# extruder-controller.net
KiCad netlist of a schematic drawn in EAGLE
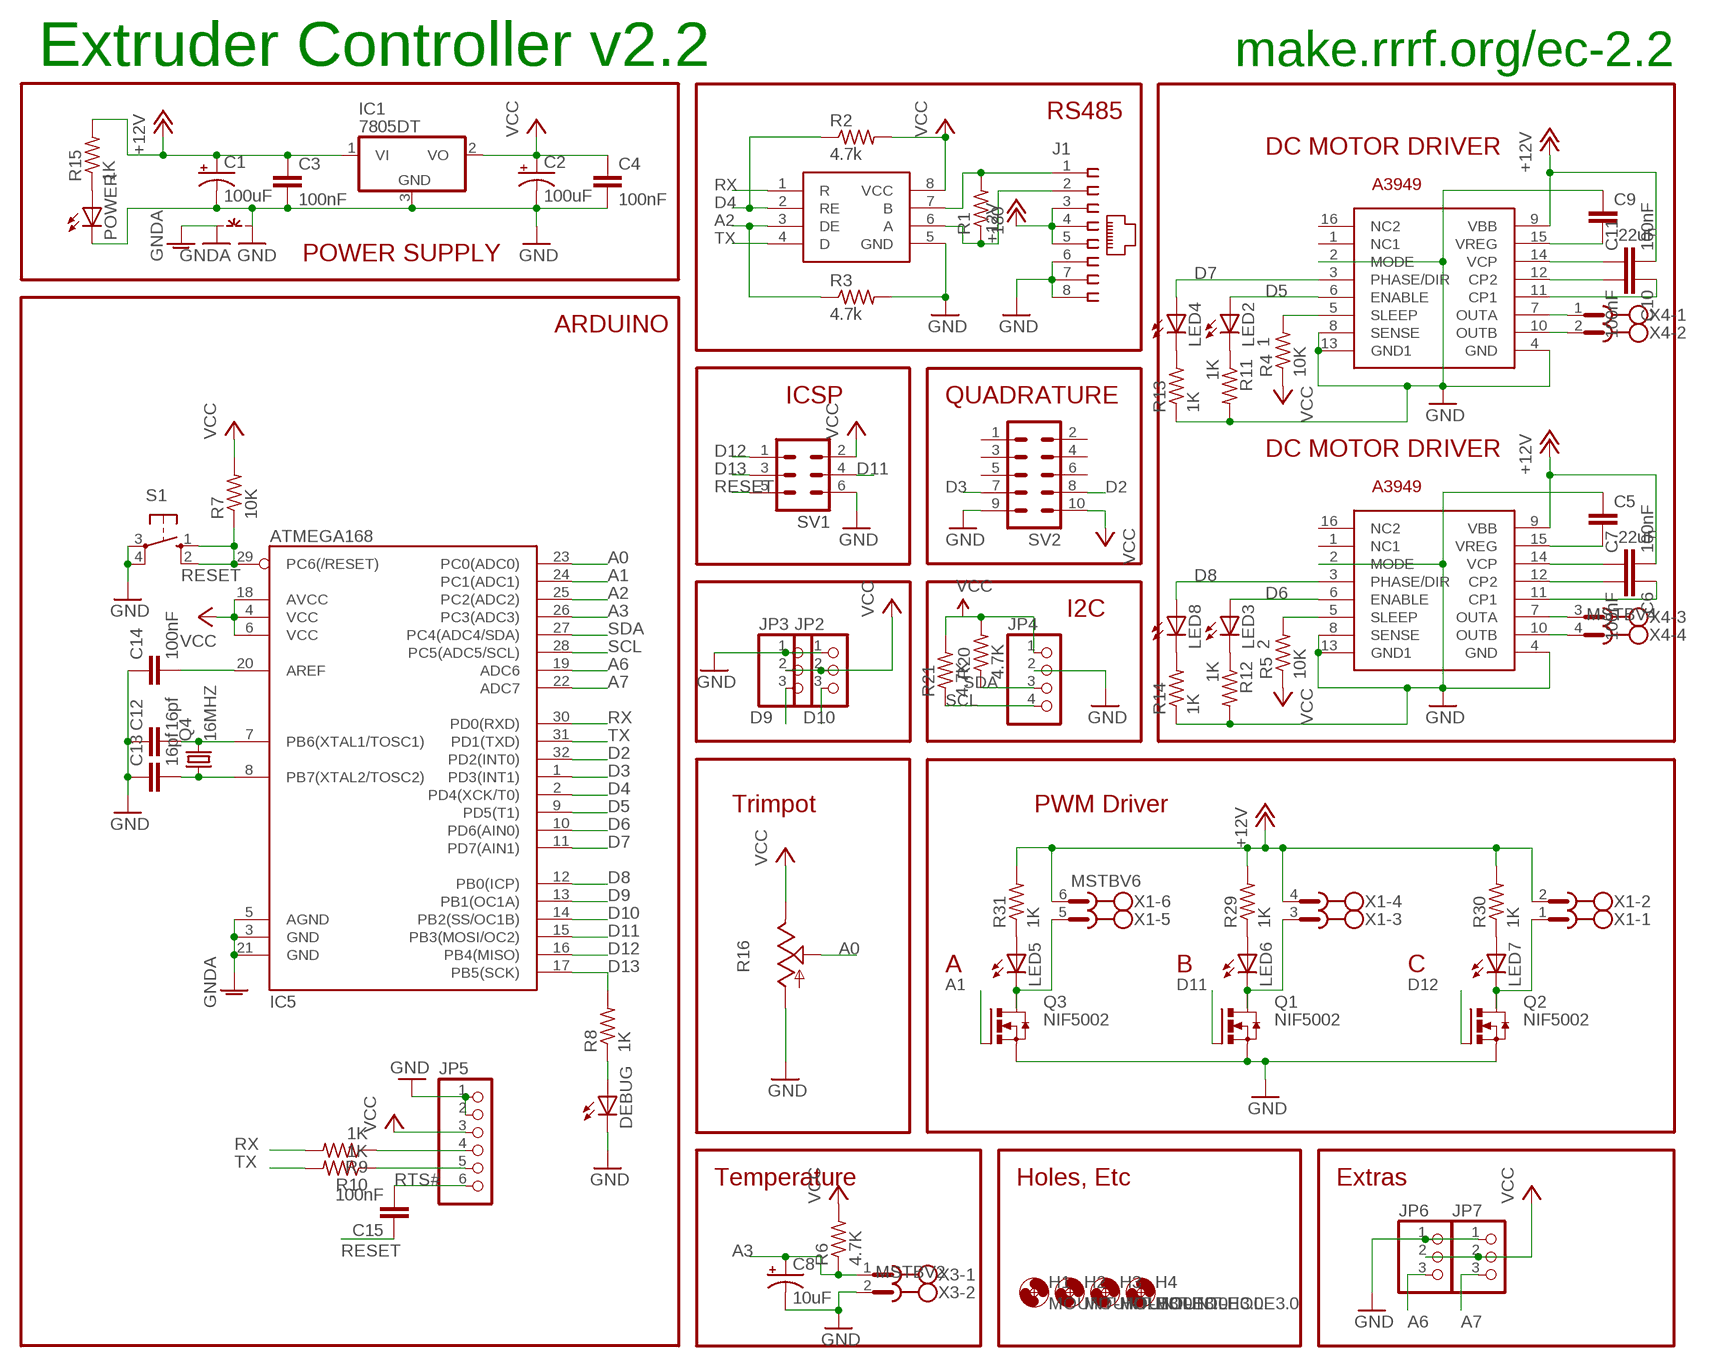
[diagram p0: schematic, sheet 1]

(export (version "E")
  (design (tool "Eeschema 10.0.6"))
  (components
    (comp (ref "C1")
      (value "100uF")
      (footprint "eagle-import:UD-10X10_NICHICON")
      (libsource (lib "eagle-import") (part "CPOL-USUD-10X10"))
    )
    (comp (ref "C2")
      (value "100uF")
      (footprint "eagle-import:UD-10X10_NICHICON")
      (libsource (lib "eagle-import") (part "CPOL-USUD-10X10"))
    )
    (comp (ref "C3")
      (value "100nF")
      (footprint "eagle-import:C1206")
      (libsource (lib "eagle-import") (part "C-EUC1206"))
    )
    (comp (ref "C4")
      (value "100nF")
      (footprint "eagle-import:C1206")
      (libsource (lib "eagle-import") (part "C-EUC1206"))
    )
    (comp (ref "C5")
      (value ".22uF")
      (footprint "eagle-import:C1206K")
      (libsource (lib "eagle-import") (part "C-EUC1206K"))
    )
    (comp (ref "C6")
      (value "100nF")
      (footprint "eagle-import:C1206K")
      (libsource (lib "eagle-import") (part "C-EUC1206K"))
    )
    (comp (ref "C7")
      (value "100nF")
      (footprint "eagle-import:C1206K")
      (libsource (lib "eagle-import") (part "C-EUC1206K"))
    )
    (comp (ref "C8")
      (value "10uF")
      (footprint "eagle-import:UD-6,3X5,8_NICHICON")
      (libsource (lib "eagle-import") (part "CPOL-USUD-6,3X5,8"))
    )
    (comp (ref "C9")
      (value ".22uF")
      (footprint "eagle-import:C1206K")
      (libsource (lib "eagle-import") (part "C-EUC1206K"))
    )
    (comp (ref "C10")
      (value "100nF")
      (footprint "eagle-import:C1206K")
      (libsource (lib "eagle-import") (part "C-EUC1206K"))
    )
    (comp (ref "C11")
      (value "100nF")
      (footprint "eagle-import:C1206K")
      (libsource (lib "eagle-import") (part "C-EUC1206K"))
    )
    (comp (ref "C12")
      (value "16pf")
      (footprint "eagle-import:C1206")
      (libsource (lib "eagle-import") (part "resistor_C-EUC1206"))
    )
    (comp (ref "C13")
      (value "16pf")
      (footprint "eagle-import:C1206")
      (libsource (lib "eagle-import") (part "resistor_C-EUC1206"))
    )
    (comp (ref "C14")
      (value "100nF")
      (footprint "eagle-import:C1206")
      (libsource (lib "eagle-import") (part "C-EUC1206"))
    )
    (comp (ref "C15")
      (value "100nF")
      (footprint "eagle-import:C1206")
      (libsource (lib "eagle-import") (part "resistor_C-EUC1206"))
    )
    (comp (ref "DEBUG")
      (value "LEDCHIPLED_1206")
      (footprint "eagle-import:CHIPLED_1206")
      (libsource (lib "eagle-import") (part "LEDCHIPLED_1206"))
    )
    (comp (ref "H1")
      (value "MOUNT-HOLE3.0")
      (footprint "eagle-import:3,0")
      (libsource (lib "eagle-import") (part "MOUNT-HOLE3.0"))
    )
    (comp (ref "H2")
      (value "MOUNT-HOLE3.0")
      (footprint "eagle-import:3,0")
      (libsource (lib "eagle-import") (part "MOUNT-HOLE3.0"))
    )
    (comp (ref "H3")
      (value "MOUNT-HOLE3.0")
      (footprint "eagle-import:3,0")
      (libsource (lib "eagle-import") (part "MOUNT-HOLE3.0"))
    )
    (comp (ref "H4")
      (value "MOUNT-HOLE3.0")
      (footprint "eagle-import:3,0")
      (libsource (lib "eagle-import") (part "MOUNT-HOLE3.0"))
    )
    (comp (ref "IC1")
      (value "7805DT")
      (footprint "eagle-import:TO252")
      (libsource (lib "eagle-import") (part "78DT05"))
    )
    (comp (ref "IC2")
      (value "A3949")
      (footprint "eagle-import:SO16W")
      (libsource (lib "eagle-import") (part "A3949"))
    )
    (comp (ref "IC3")
      (value "A3949")
      (footprint "eagle-import:SO16W")
      (libsource (lib "eagle-import") (part "A3949"))
    )
    (comp (ref "IC4")
      (value "SN75176ASOIC")
      (footprint "eagle-import:SO08")
      (libsource (lib "eagle-import") (part "SN75176ASOIC"))
    )
    (comp (ref "IC5")
      (value "ATMEGA168")
      (footprint "eagle-import:TQFP32-08")
      (libsource (lib "eagle-import") (part "ATMEGA168"))
    )
    (comp (ref "J1")
      (value "520426-4")
      (footprint "eagle-import:520426-4")
      (libsource (lib "eagle-import") (part "520426-4"))
    )
    (comp (ref "JP2")
      (value "PINHD-1X3")
      (footprint "eagle-import:1X03")
      (libsource (lib "eagle-import") (part "PINHD-1X3"))
    )
    (comp (ref "JP3")
      (value "PINHD-1X3")
      (footprint "eagle-import:1X03")
      (libsource (lib "eagle-import") (part "PINHD-1X3"))
    )
    (comp (ref "JP4")
      (value "PINHD-1X4")
      (footprint "eagle-import:1X04")
      (libsource (lib "eagle-import") (part "PINHD-1X4"))
    )
    (comp (ref "JP5")
      (value "PINHD-1X6")
      (footprint "eagle-import:1X06")
      (libsource (lib "eagle-import") (part "PINHD-1X6"))
    )
    (comp (ref "JP6")
      (value "PINHD-1X3")
      (footprint "eagle-import:1X03")
      (libsource (lib "eagle-import") (part "PINHD-1X3"))
    )
    (comp (ref "JP7")
      (value "PINHD-1X3")
      (footprint "eagle-import:1X03")
      (libsource (lib "eagle-import") (part "PINHD-1X3"))
    )
    (comp (ref "LED2")
      (value "1")
      (footprint "eagle-import:CHIPLED_1206")
      (libsource (lib "eagle-import") (part "LEDCHIPLED_1206"))
    )
    (comp (ref "LED3")
      (value "2")
      (footprint "eagle-import:CHIPLED_1206")
      (libsource (lib "eagle-import") (part "LEDCHIPLED_1206"))
    )
    (comp (ref "LED4")
      (value "LEDCHIPLED_1206")
      (footprint "eagle-import:CHIPLED_1206")
      (libsource (lib "eagle-import") (part "LEDCHIPLED_1206"))
    )
    (comp (ref "LED5")
      (value "LEDCHIPLED_1206")
      (footprint "eagle-import:CHIPLED_1206")
      (libsource (lib "eagle-import") (part "LEDCHIPLED_1206"))
    )
    (comp (ref "LED6")
      (value "LEDCHIPLED_1206")
      (footprint "eagle-import:CHIPLED_1206")
      (libsource (lib "eagle-import") (part "LEDCHIPLED_1206"))
    )
    (comp (ref "LED7")
      (value "LEDCHIPLED_1206")
      (footprint "eagle-import:CHIPLED_1206")
      (libsource (lib "eagle-import") (part "LEDCHIPLED_1206"))
    )
    (comp (ref "LED8")
      (value "LEDCHIPLED_1206")
      (footprint "eagle-import:CHIPLED_1206")
      (libsource (lib "eagle-import") (part "LEDCHIPLED_1206"))
    )
    (comp (ref "POWER")
      (value "LEDCHIPLED_1206")
      (footprint "eagle-import:CHIPLED_1206")
      (libsource (lib "eagle-import") (part "LEDCHIPLED_1206"))
    )
    (comp (ref "Q1")
      (value "NIF5002")
      (footprint "eagle-import:SOT223")
      (libsource (lib "eagle-import") (part "N-HEXFET-2D_?-SOT232"))
    )
    (comp (ref "Q2")
      (value "NIF5002")
      (footprint "eagle-import:SOT223")
      (libsource (lib "eagle-import") (part "N-HEXFET-2D_?-SOT232"))
    )
    (comp (ref "Q3")
      (value "NIF5002")
      (footprint "eagle-import:SOT223")
      (libsource (lib "eagle-import") (part "N-HEXFET-2D_?-SOT232"))
    )
    (comp (ref "Q4")
      (value "16MHZ")
      (footprint "eagle-import:HC49_S")
      (libsource (lib "eagle-import") (part "CRYSTALHC49S"))
    )
    (comp (ref "R1")
      (value "180")
      (footprint "eagle-import:R1206")
      (libsource (lib "eagle-import") (part "resistor_R-US_R1206"))
    )
    (comp (ref "R2")
      (value "4.7k")
      (footprint "eagle-import:R1206")
      (libsource (lib "eagle-import") (part "resistor_R-US_R1206"))
    )
    (comp (ref "R3")
      (value "4.7k")
      (footprint "eagle-import:R1206")
      (libsource (lib "eagle-import") (part "resistor_R-US_R1206"))
    )
    (comp (ref "R4")
      (value "10K")
      (footprint "eagle-import:R1206")
      (libsource (lib "eagle-import") (part "resistor_R-US_R1206"))
    )
    (comp (ref "R5")
      (value "10K")
      (footprint "eagle-import:R1206")
      (libsource (lib "eagle-import") (part "resistor_R-US_R1206"))
    )
    (comp (ref "R6")
      (value "4.7K")
      (footprint "eagle-import:M1206")
      (libsource (lib "eagle-import") (part "R-US_M1206"))
    )
    (comp (ref "R7")
      (value "10K")
      (footprint "eagle-import:R1206")
      (libsource (lib "eagle-import") (part "resistor_R-US_R1206"))
    )
    (comp (ref "R8")
      (value "1K")
      (footprint "eagle-import:R1206")
      (libsource (lib "eagle-import") (part "resistor_R-US_R1206"))
    )
    (comp (ref "R9")
      (value "1K")
      (footprint "eagle-import:R1206")
      (libsource (lib "eagle-import") (part "resistor_R-US_R1206"))
    )
    (comp (ref "R10")
      (value "1K")
      (footprint "eagle-import:R1206")
      (libsource (lib "eagle-import") (part "resistor_R-US_R1206"))
    )
    (comp (ref "R11")
      (value "1K")
      (footprint "eagle-import:R1206")
      (libsource (lib "eagle-import") (part "R-US_R1206"))
    )
    (comp (ref "R12")
      (value "1K")
      (footprint "eagle-import:R1206")
      (libsource (lib "eagle-import") (part "R-US_R1206"))
    )
    (comp (ref "R13")
      (value "1K")
      (footprint "eagle-import:R1206")
      (libsource (lib "eagle-import") (part "R-US_R1206"))
    )
    (comp (ref "R14")
      (value "1K")
      (footprint "eagle-import:R1206")
      (libsource (lib "eagle-import") (part "R-US_R1206"))
    )
    (comp (ref "R15")
      (value "1K")
      (footprint "eagle-import:R1206")
      (libsource (lib "eagle-import") (part "resistor_R-US_R1206"))
    )
    (comp (ref "R16")
      (value "TRIM_US-B25P")
      (footprint "eagle-import:B25P")
      (libsource (lib "eagle-import") (part "TRIM_US-B25P"))
    )
    (comp (ref "R20")
      (value "4.7K")
      (footprint "eagle-import:R1206")
      (libsource (lib "eagle-import") (part "R-US_R1206"))
    )
    (comp (ref "R21")
      (value "4.7K")
      (footprint "eagle-import:R1206")
      (libsource (lib "eagle-import") (part "R-US_R1206"))
    )
    (comp (ref "R29")
      (value "1K")
      (footprint "eagle-import:R1206")
      (libsource (lib "eagle-import") (part "R-US_R1206"))
    )
    (comp (ref "R30")
      (value "1K")
      (footprint "eagle-import:R1206")
      (libsource (lib "eagle-import") (part "R-US_R1206"))
    )
    (comp (ref "R31")
      (value "1K")
      (footprint "eagle-import:M1206")
      (libsource (lib "eagle-import") (part "R-US_M1206"))
    )
    (comp (ref "S1")
      (value "10-XX")
      (footprint "eagle-import:B3F-10XX")
      (libsource (lib "eagle-import") (part "10-XX"))
    )
    (comp (ref "SV1")
      (value "ML6")
      (footprint "eagle-import:ML6")
      (libsource (lib "eagle-import") (part "ML6"))
    )
    (comp (ref "SV2")
      (value "ML10")
      (footprint "eagle-import:ML10")
      (libsource (lib "eagle-import") (part "ML10"))
    )
    (comp (ref "X1")
      (value "MSTBV6")
      (footprint "eagle-import:MSTBV6")
      (libsource (lib "eagle-import") (part "MSTBV6"))
    )
    (comp (ref "X3")
      (value "MSTBV2")
      (footprint "eagle-import:MSTBV2")
      (libsource (lib "eagle-import") (part "MSTBV2"))
    )
    (comp (ref "X4")
      (value "MSTBV4")
      (footprint "eagle-import:MSTBV4")
      (libsource (lib "eagle-import") (part "MSTBV4"))
    )
    (comp (ref "~NUDEV~1")
      (value "GND-GNDA")
      (footprint "eagle-import:GND-GNDA")
      (libsource (lib "eagle-import") (part "GND-GNDA"))
    )
  )
  (nets
    (net (code "1") (name "+12V") (class "Default")
      (node (ref "C1") (pin "+") (pinfunction "+_+") (pintype "passive"))
      (node (ref "C11") (pin "2") (pinfunction "2_2") (pintype "passive"))
      (node (ref "C3") (pin "1") (pinfunction "1_1") (pintype "passive"))
      (node (ref "C7") (pin "2") (pinfunction "2_2") (pintype "passive"))
      (node (ref "IC1") (pin "1") (pinfunction "VI_1") (pintype "input"))
      (node (ref "IC2") (pin "9") (pinfunction "VBB_9") (pintype "bidirectional"))
      (node (ref "IC3") (pin "9") (pinfunction "VBB_9") (pintype "bidirectional"))
      (node (ref "J1") (pin "3") (pinfunction "3_3") (pintype "passive"))
      (node (ref "J1") (pin "4") (pinfunction "4_4") (pintype "passive"))
      (node (ref "J1") (pin "5") (pinfunction "5_5") (pintype "passive"))
      (node (ref "R15") (pin "2") (pinfunction "2_2") (pintype "passive"))
      (node (ref "R29") (pin "2") (pinfunction "2_2") (pintype "passive"))
      (node (ref "R30") (pin "2") (pinfunction "2_2") (pintype "passive"))
      (node (ref "R31") (pin "2") (pinfunction "2_2") (pintype "passive"))
      (node (ref "X1") (pin "2") (pinfunction "1_2") (pintype "passive"))
      (node (ref "X1") (pin "4") (pinfunction "1_4") (pintype "passive"))
      (node (ref "X1") (pin "6") (pinfunction "1_6") (pintype "passive"))
    )
    (net (code "2") (name "/A0") (class "Default")
      (node (ref "IC5") (pin "23") (pinfunction "PC0(ADC0)_23") (pintype "bidirectional"))
      (node (ref "R16") (pin "S") (pinfunction "S_S") (pintype "passive"))
    )
    (net (code "3") (name "/A1") (class "Default")
      (node (ref "IC5") (pin "24") (pinfunction "PC1(ADC1)_24") (pintype "bidirectional"))
      (node (ref "Q3") (pin "1") (pinfunction "G_1") (pintype "passive"))
    )
    (net (code "4") (name "/A2") (class "Default")
      (node (ref "IC4") (pin "3") (pinfunction "DE_3") (pintype "bidirectional"))
      (node (ref "IC5") (pin "25") (pinfunction "PC2(ADC2)_25") (pintype "bidirectional"))
      (node (ref "R3") (pin "1") (pinfunction "1_1") (pintype "passive"))
    )
    (net (code "5") (name "/A3") (class "Default")
      (node (ref "C8") (pin "+") (pinfunction "+_+") (pintype "passive"))
      (node (ref "IC5") (pin "26") (pinfunction "PC3(ADC3)_26") (pintype "bidirectional"))
      (node (ref "R6") (pin "1") (pinfunction "1_1") (pintype "passive"))
      (node (ref "X3") (pin "1") (pinfunction "1_1") (pintype "passive"))
    )
    (net (code "6") (name "/A6") (class "Default")
      (node (ref "IC5") (pin "19") (pinfunction "ADC6_19") (pintype "bidirectional"))
      (node (ref "JP6") (pin "3") (pinfunction "3_3") (pintype "passive"))
    )
    (net (code "7") (name "/A7") (class "Default")
      (node (ref "IC5") (pin "22") (pinfunction "ADC7_22") (pintype "bidirectional"))
      (node (ref "JP7") (pin "3") (pinfunction "3_3") (pintype "passive"))
    )
    (net (code "8") (name "/D2") (class "Default")
      (node (ref "IC5") (pin "32") (pinfunction "PD2(INT0)_32") (pintype "bidirectional"))
      (node (ref "SV2") (pin "8") (pinfunction "8_8") (pintype "passive"))
    )
    (net (code "9") (name "/D3") (class "Default")
      (node (ref "IC5") (pin "1") (pinfunction "PD3(INT1)_1") (pintype "bidirectional"))
      (node (ref "SV2") (pin "7") (pinfunction "7_7") (pintype "passive"))
    )
    (net (code "10") (name "/D4") (class "Default")
      (node (ref "IC4") (pin "2") (pinfunction "RE_2") (pintype "bidirectional"))
      (node (ref "IC5") (pin "2") (pinfunction "PD4(XCK/T0)_2") (pintype "bidirectional"))
      (node (ref "R2") (pin "1") (pinfunction "1_1") (pintype "passive"))
    )
    (net (code "11") (name "/D5") (class "Default")
      (node (ref "IC2") (pin "6") (pinfunction "ENABLE_6") (pintype "bidirectional"))
      (node (ref "IC5") (pin "9") (pinfunction "PD5(T1)_9") (pintype "bidirectional"))
      (node (ref "LED2") (pin "A") (pinfunction "A_A") (pintype "passive"))
    )
    (net (code "12") (name "/D6") (class "Default")
      (node (ref "IC3") (pin "6") (pinfunction "ENABLE_6") (pintype "bidirectional"))
      (node (ref "IC5") (pin "10") (pinfunction "PD6(AIN0)_10") (pintype "bidirectional"))
      (node (ref "LED3") (pin "A") (pinfunction "A_A") (pintype "passive"))
    )
    (net (code "13") (name "/D7") (class "Default")
      (node (ref "IC2") (pin "3") (pinfunction "PHASE/DIR_3") (pintype "bidirectional"))
      (node (ref "IC5") (pin "11") (pinfunction "PD7(AIN1)_11") (pintype "bidirectional"))
      (node (ref "LED4") (pin "A") (pinfunction "A_A") (pintype "passive"))
    )
    (net (code "14") (name "/D8") (class "Default")
      (node (ref "IC3") (pin "3") (pinfunction "PHASE/DIR_3") (pintype "bidirectional"))
      (node (ref "IC5") (pin "12") (pinfunction "PB0(ICP)_12") (pintype "bidirectional"))
      (node (ref "LED8") (pin "A") (pinfunction "A_A") (pintype "passive"))
    )
    (net (code "15") (name "/D9") (class "Default")
      (node (ref "IC5") (pin "13") (pinfunction "PB1(OC1A)_13") (pintype "bidirectional"))
      (node (ref "JP3") (pin "3") (pinfunction "3_3") (pintype "passive"))
    )
    (net (code "16") (name "/D10") (class "Default")
      (node (ref "IC5") (pin "14") (pinfunction "PB2(SS/OC1B)_14") (pintype "bidirectional"))
      (node (ref "JP2") (pin "3") (pinfunction "3_3") (pintype "passive"))
    )
    (net (code "17") (name "/D11") (class "Default")
      (node (ref "IC5") (pin "15") (pinfunction "PB3(MOSI/OC2)_15") (pintype "bidirectional"))
      (node (ref "Q1") (pin "1") (pinfunction "G_1") (pintype "passive"))
      (node (ref "SV1") (pin "4") (pinfunction "4_4") (pintype "passive"))
    )
    (net (code "18") (name "/D12") (class "Default")
      (node (ref "IC5") (pin "16") (pinfunction "PB4(MISO)_16") (pintype "bidirectional"))
      (node (ref "Q2") (pin "1") (pinfunction "G_1") (pintype "passive"))
      (node (ref "SV1") (pin "1") (pinfunction "1_1") (pintype "passive"))
    )
    (net (code "19") (name "/D13") (class "Default")
      (node (ref "IC5") (pin "17") (pinfunction "PB5(SCK)_17") (pintype "bidirectional"))
      (node (ref "R8") (pin "2") (pinfunction "2_2") (pintype "passive"))
      (node (ref "SV1") (pin "3") (pinfunction "3_3") (pintype "passive"))
    )
    (net (code "20") (name "/RESET") (class "Default")
      (node (ref "C15") (pin "1") (pinfunction "1_1") (pintype "passive"))
      (node (ref "IC5") (pin "29") (pinfunction "PC6(/RESET)_29") (pintype "bidirectional"))
      (node (ref "R7") (pin "1") (pinfunction "1_1") (pintype "passive"))
      (node (ref "S1") (pin "1") (pinfunction "S_1") (pintype "passive"))
      (node (ref "S1") (pin "2") (pinfunction "S1_2") (pintype "passive"))
      (node (ref "SV1") (pin "5") (pinfunction "5_5") (pintype "passive"))
    )
    (net (code "21") (name "/RTS#") (class "Default")
      (node (ref "C15") (pin "2") (pinfunction "2_2") (pintype "passive"))
      (node (ref "JP5") (pin "6") (pinfunction "6_6") (pintype "passive"))
    )
    (net (code "22") (name "/RX") (class "Default")
      (node (ref "IC4") (pin "1") (pinfunction "R_1") (pintype "bidirectional"))
      (node (ref "IC5") (pin "30") (pinfunction "PD0(RXD)_30") (pintype "bidirectional"))
      (node (ref "R9") (pin "2") (pinfunction "2_2") (pintype "passive"))
    )
    (net (code "23") (name "/SCL") (class "Default")
      (node (ref "IC5") (pin "28") (pinfunction "PC5(ADC5/SCL)_28") (pintype "bidirectional"))
      (node (ref "JP4") (pin "4") (pinfunction "4_4") (pintype "passive"))
      (node (ref "R21") (pin "1") (pinfunction "1_1") (pintype "passive"))
    )
    (net (code "24") (name "/SDA") (class "Default")
      (node (ref "IC5") (pin "27") (pinfunction "PC4(ADC4/SDA)_27") (pintype "bidirectional"))
      (node (ref "JP4") (pin "3") (pinfunction "3_3") (pintype "passive"))
      (node (ref "R20") (pin "1") (pinfunction "1_1") (pintype "passive"))
    )
    (net (code "25") (name "/TX") (class "Default")
      (node (ref "IC4") (pin "4") (pinfunction "D_4") (pintype "bidirectional"))
      (node (ref "IC5") (pin "31") (pinfunction "PD1(TXD)_31") (pintype "bidirectional"))
      (node (ref "R10") (pin "2") (pinfunction "2_2") (pintype "passive"))
    )
    (net (code "26") (name "GND") (class "Default")
      (node (ref "C1") (pin "-") (pinfunction "-_-") (pintype "passive"))
      (node (ref "C12") (pin "1") (pinfunction "1_1") (pintype "passive"))
      (node (ref "C13") (pin "1") (pinfunction "1_1") (pintype "passive"))
      (node (ref "C14") (pin "1") (pinfunction "1_1") (pintype "passive"))
      (node (ref "C2") (pin "-") (pinfunction "-_-") (pintype "passive"))
      (node (ref "C3") (pin "2") (pinfunction "2_2") (pintype "passive"))
      (node (ref "C4") (pin "2") (pinfunction "2_2") (pintype "passive"))
      (node (ref "C5") (pin "1") (pinfunction "1_1") (pintype "passive"))
      (node (ref "C8") (pin "-") (pinfunction "-_-") (pintype "passive"))
      (node (ref "C9") (pin "1") (pinfunction "1_1") (pintype "passive"))
      (node (ref "DEBUG") (pin "C") (pinfunction "C_C") (pintype "passive"))
      (node (ref "IC1") (pin "3") (pinfunction "GND_3") (pintype "passive"))
      (node (ref "IC2") (pin "13") (pinfunction "GND1_13") (pintype "bidirectional"))
      (node (ref "IC2") (pin "2") (pinfunction "MODE_2") (pintype "bidirectional"))
      (node (ref "IC2") (pin "4") (pinfunction "GND_4") (pintype "bidirectional"))
      (node (ref "IC2") (pin "8") (pinfunction "SENSE_8") (pintype "bidirectional"))
      (node (ref "IC3") (pin "13") (pinfunction "GND1_13") (pintype "bidirectional"))
      (node (ref "IC3") (pin "2") (pinfunction "MODE_2") (pintype "bidirectional"))
      (node (ref "IC3") (pin "4") (pinfunction "GND_4") (pintype "bidirectional"))
      (node (ref "IC3") (pin "8") (pinfunction "SENSE_8") (pintype "bidirectional"))
      (node (ref "IC4") (pin "5") (pinfunction "GND_5") (pintype "bidirectional"))
      (node (ref "J1") (pin "6") (pinfunction "6_6") (pintype "passive"))
      (node (ref "J1") (pin "7") (pinfunction "7_7") (pintype "passive"))
      (node (ref "J1") (pin "8") (pinfunction "8_8") (pintype "passive"))
      (node (ref "JP2") (pin "1") (pinfunction "1_1") (pintype "passive"))
      (node (ref "JP3") (pin "1") (pinfunction "1_1") (pintype "passive"))
      (node (ref "JP4") (pin "2") (pinfunction "2_2") (pintype "passive"))
      (node (ref "JP5") (pin "1") (pinfunction "1_1") (pintype "passive"))
      (node (ref "JP5") (pin "2") (pinfunction "2_2") (pintype "passive"))
      (node (ref "JP6") (pin "1") (pinfunction "1_1") (pintype "passive"))
      (node (ref "JP7") (pin "1") (pinfunction "1_1") (pintype "passive"))
      (node (ref "POWER") (pin "C") (pinfunction "C_C") (pintype "passive"))
      (node (ref "Q1") (pin "3") (pinfunction "S_3") (pintype "passive"))
      (node (ref "Q2") (pin "3") (pinfunction "S_3") (pintype "passive"))
      (node (ref "Q3") (pin "3") (pinfunction "S_3") (pintype "passive"))
      (node (ref "R11") (pin "2") (pinfunction "2_2") (pintype "passive"))
      (node (ref "R12") (pin "2") (pinfunction "2_2") (pintype "passive"))
      (node (ref "R13") (pin "1") (pinfunction "1_1") (pintype "passive"))
      (node (ref "R14") (pin "1") (pinfunction "1_1") (pintype "passive"))
      (node (ref "R16") (pin "A") (pinfunction "A_A") (pintype "passive"))
      (node (ref "R3") (pin "2") (pinfunction "2_2") (pintype "passive"))
      (node (ref "S1") (pin "3") (pinfunction "P_3") (pintype "passive"))
      (node (ref "S1") (pin "4") (pinfunction "P1_4") (pintype "passive"))
      (node (ref "SV1") (pin "6") (pinfunction "6_6") (pintype "passive"))
      (node (ref "SV2") (pin "9") (pinfunction "9_9") (pintype "passive"))
      (node (ref "X3") (pin "2") (pinfunction "1_2") (pintype "passive"))
      (node (ref "~NUDEV~1") (pin "GND") (pinfunction "GND_GND") (pintype "power_in"))
    )
    (net (code "27") (name "GNDA") (class "Default")
      (node (ref "IC5") (pin "21") (pinfunction "GND_21") (pintype "bidirectional"))
      (node (ref "IC5") (pin "3") (pinfunction "GND_3") (pintype "bidirectional"))
      (node (ref "IC5") (pin "5") (pinfunction "AGND_5") (pintype "bidirectional"))
      (node (ref "~NUDEV~1") (pin "GNDA") (pinfunction "GNDA_GNDA") (pintype "power_in"))
    )
    (net (code "28") (name "Net-(DEBUG-PadA)") (class "Default")
      (node (ref "DEBUG") (pin "A") (pinfunction "A_A") (pintype "passive"))
      (node (ref "R8") (pin "1") (pinfunction "1_1") (pintype "passive"))
    )
    (net (code "29") (name "Net-(IC2-CP1)") (class "Default")
      (node (ref "C10") (pin "1") (pinfunction "1_1") (pintype "passive"))
      (node (ref "IC2") (pin "11") (pinfunction "CP1_11") (pintype "bidirectional"))
    )
    (net (code "30") (name "Net-(IC2-CP2)") (class "Default")
      (node (ref "C10") (pin "2") (pinfunction "2_2") (pintype "passive"))
      (node (ref "IC2") (pin "12") (pinfunction "CP2_12") (pintype "bidirectional"))
    )
    (net (code "31") (name "Net-(IC2-OUTA)") (class "Default")
      (node (ref "IC2") (pin "7") (pinfunction "OUTA_7") (pintype "bidirectional"))
      (node (ref "X4") (pin "1") (pinfunction "1_1") (pintype "passive"))
    )
    (net (code "32") (name "Net-(IC2-OUTB)") (class "Default")
      (node (ref "IC2") (pin "10") (pinfunction "OUTB_10") (pintype "bidirectional"))
      (node (ref "X4") (pin "2") (pinfunction "1_2") (pintype "passive"))
    )
    (net (code "33") (name "Net-(IC2-SLEEP)") (class "Default")
      (node (ref "IC2") (pin "5") (pinfunction "SLEEP_5") (pintype "bidirectional"))
      (node (ref "R4") (pin "2") (pinfunction "2_2") (pintype "passive"))
    )
    (net (code "34") (name "Net-(IC2-VCP)") (class "Default")
      (node (ref "C11") (pin "1") (pinfunction "1_1") (pintype "passive"))
      (node (ref "IC2") (pin "14") (pinfunction "VCP_14") (pintype "bidirectional"))
    )
    (net (code "35") (name "Net-(IC2-VREG)") (class "Default")
      (node (ref "C9") (pin "2") (pinfunction "2_2") (pintype "passive"))
      (node (ref "IC2") (pin "15") (pinfunction "VREG_15") (pintype "bidirectional"))
    )
    (net (code "36") (name "Net-(IC3-CP1)") (class "Default")
      (node (ref "C6") (pin "1") (pinfunction "1_1") (pintype "passive"))
      (node (ref "IC3") (pin "11") (pinfunction "CP1_11") (pintype "bidirectional"))
    )
    (net (code "37") (name "Net-(IC3-CP2)") (class "Default")
      (node (ref "C6") (pin "2") (pinfunction "2_2") (pintype "passive"))
      (node (ref "IC3") (pin "12") (pinfunction "CP2_12") (pintype "bidirectional"))
    )
    (net (code "38") (name "Net-(IC3-OUTA)") (class "Default")
      (node (ref "IC3") (pin "7") (pinfunction "OUTA_7") (pintype "bidirectional"))
      (node (ref "X4") (pin "3") (pinfunction "1_3") (pintype "passive"))
    )
    (net (code "39") (name "Net-(IC3-OUTB)") (class "Default")
      (node (ref "IC3") (pin "10") (pinfunction "OUTB_10") (pintype "bidirectional"))
      (node (ref "X4") (pin "4") (pinfunction "1_4") (pintype "passive"))
    )
    (net (code "40") (name "Net-(IC3-SLEEP)") (class "Default")
      (node (ref "IC3") (pin "5") (pinfunction "SLEEP_5") (pintype "bidirectional"))
      (node (ref "R5") (pin "2") (pinfunction "2_2") (pintype "passive"))
    )
    (net (code "41") (name "Net-(IC3-VCP)") (class "Default")
      (node (ref "C7") (pin "1") (pinfunction "1_1") (pintype "passive"))
      (node (ref "IC3") (pin "14") (pinfunction "VCP_14") (pintype "bidirectional"))
    )
    (net (code "42") (name "Net-(IC3-VREG)") (class "Default")
      (node (ref "C5") (pin "2") (pinfunction "2_2") (pintype "passive"))
      (node (ref "IC3") (pin "15") (pinfunction "VREG_15") (pintype "bidirectional"))
    )
    (net (code "43") (name "Net-(IC4-A)") (class "Default")
      (node (ref "IC4") (pin "6") (pinfunction "A_6") (pintype "bidirectional"))
      (node (ref "J1") (pin "2") (pinfunction "2_2") (pintype "passive"))
      (node (ref "R1") (pin "1") (pinfunction "1_1") (pintype "passive"))
    )
    (net (code "44") (name "Net-(IC4-B)") (class "Default")
      (node (ref "IC4") (pin "7") (pinfunction "B_7") (pintype "bidirectional"))
      (node (ref "J1") (pin "1") (pinfunction "1_1") (pintype "passive"))
      (node (ref "R1") (pin "2") (pinfunction "2_2") (pintype "passive"))
    )
    (net (code "45") (name "Net-(IC5-AREF)") (class "Default")
      (node (ref "C14") (pin "2") (pinfunction "2_2") (pintype "passive"))
      (node (ref "IC5") (pin "20") (pinfunction "AREF_20") (pintype "bidirectional"))
    )
    (net (code "46") (name "Net-(IC5-PB6(XTAL1{slash}TOSC1))") (class "Default")
      (node (ref "C12") (pin "2") (pinfunction "2_2") (pintype "passive"))
      (node (ref "IC5") (pin "7") (pinfunction "PB6(XTAL1/TOSC1)_7") (pintype "bidirectional"))
      (node (ref "Q4") (pin "2") (pinfunction "2_2") (pintype "passive"))
    )
    (net (code "47") (name "Net-(IC5-PB7(XTAL2{slash}TOSC2))") (class "Default")
      (node (ref "C13") (pin "2") (pinfunction "2_2") (pintype "passive"))
      (node (ref "IC5") (pin "8") (pinfunction "PB7(XTAL2/TOSC2)_8") (pintype "bidirectional"))
      (node (ref "Q4") (pin "1") (pinfunction "1_1") (pintype "passive"))
    )
    (net (code "48") (name "Net-(JP5-Pad4)") (class "Default")
      (node (ref "JP5") (pin "4") (pinfunction "4_4") (pintype "passive"))
      (node (ref "R9") (pin "1") (pinfunction "1_1") (pintype "passive"))
    )
    (net (code "49") (name "Net-(JP5-Pad5)") (class "Default")
      (node (ref "JP5") (pin "5") (pinfunction "5_5") (pintype "passive"))
      (node (ref "R10") (pin "1") (pinfunction "1_1") (pintype "passive"))
    )
    (net (code "50") (name "Net-(LED2-PadC)") (class "Default")
      (node (ref "LED2") (pin "C") (pinfunction "C_C") (pintype "passive"))
      (node (ref "R11") (pin "1") (pinfunction "1_1") (pintype "passive"))
    )
    (net (code "51") (name "Net-(LED3-PadC)") (class "Default")
      (node (ref "LED3") (pin "C") (pinfunction "C_C") (pintype "passive"))
      (node (ref "R12") (pin "1") (pinfunction "1_1") (pintype "passive"))
    )
    (net (code "52") (name "Net-(LED4-PadC)") (class "Default")
      (node (ref "LED4") (pin "C") (pinfunction "C_C") (pintype "passive"))
      (node (ref "R13") (pin "2") (pinfunction "2_2") (pintype "passive"))
    )
    (net (code "53") (name "Net-(LED5-PadA)") (class "Default")
      (node (ref "LED5") (pin "A") (pinfunction "A_A") (pintype "passive"))
      (node (ref "R31") (pin "1") (pinfunction "1_1") (pintype "passive"))
    )
    (net (code "54") (name "Net-(LED6-PadA)") (class "Default")
      (node (ref "LED6") (pin "A") (pinfunction "A_A") (pintype "passive"))
      (node (ref "R29") (pin "1") (pinfunction "1_1") (pintype "passive"))
    )
    (net (code "55") (name "Net-(LED7-PadA)") (class "Default")
      (node (ref "LED7") (pin "A") (pinfunction "A_A") (pintype "passive"))
      (node (ref "R30") (pin "1") (pinfunction "1_1") (pintype "passive"))
    )
    (net (code "56") (name "Net-(LED7-PadC)") (class "Default")
      (node (ref "LED7") (pin "C") (pinfunction "C_C") (pintype "passive"))
      (node (ref "Q2") (pin "2") (pinfunction "D_2") (pintype "passive"))
      (node (ref "Q2") (pin "4") (pinfunction "D_4") (pintype "passive"))
      (node (ref "X1") (pin "1") (pinfunction "1_1") (pintype "passive"))
    )
    (net (code "57") (name "Net-(LED8-PadC)") (class "Default")
      (node (ref "LED8") (pin "C") (pinfunction "C_C") (pintype "passive"))
      (node (ref "R14") (pin "2") (pinfunction "2_2") (pintype "passive"))
    )
    (net (code "58") (name "Net-(POWER-PadA)") (class "Default")
      (node (ref "POWER") (pin "A") (pinfunction "A_A") (pintype "passive"))
      (node (ref "R15") (pin "1") (pinfunction "1_1") (pintype "passive"))
    )
    (net (code "59") (name "Net-(X1C-1)") (class "Default")
      (node (ref "LED6") (pin "C") (pinfunction "C_C") (pintype "passive"))
      (node (ref "Q1") (pin "2") (pinfunction "D_2") (pintype "passive"))
      (node (ref "Q1") (pin "4") (pinfunction "D_4") (pintype "passive"))
      (node (ref "X1") (pin "3") (pinfunction "1_3") (pintype "passive"))
    )
    (net (code "60") (name "Net-(X1E-1)") (class "Default")
      (node (ref "LED5") (pin "C") (pinfunction "C_C") (pintype "passive"))
      (node (ref "Q3") (pin "2") (pinfunction "D_2") (pintype "passive"))
      (node (ref "Q3") (pin "4") (pinfunction "D_4") (pintype "passive"))
      (node (ref "X1") (pin "5") (pinfunction "1_5") (pintype "passive"))
    )
    (net (code "61") (name "VCC") (class "Default")
      (node (ref "C2") (pin "+") (pinfunction "+_+") (pintype "passive"))
      (node (ref "C4") (pin "1") (pinfunction "1_1") (pintype "passive"))
      (node (ref "IC1") (pin "2") (pinfunction "VO_2") (pintype "passive"))
      (node (ref "IC4") (pin "8") (pinfunction "VCC_8") (pintype "bidirectional"))
      (node (ref "IC5") (pin "18") (pinfunction "AVCC_18") (pintype "bidirectional"))
      (node (ref "IC5") (pin "4") (pinfunction "VCC_4") (pintype "bidirectional"))
      (node (ref "IC5") (pin "6") (pinfunction "VCC_6") (pintype "bidirectional"))
      (node (ref "JP2") (pin "2") (pinfunction "2_2") (pintype "passive"))
      (node (ref "JP3") (pin "2") (pinfunction "2_2") (pintype "passive"))
      (node (ref "JP4") (pin "1") (pinfunction "1_1") (pintype "passive"))
      (node (ref "JP5") (pin "3") (pinfunction "3_3") (pintype "passive"))
      (node (ref "JP6") (pin "2") (pinfunction "2_2") (pintype "passive"))
      (node (ref "JP7") (pin "2") (pinfunction "2_2") (pintype "passive"))
      (node (ref "R16") (pin "E") (pinfunction "E_E") (pintype "passive"))
      (node (ref "R2") (pin "2") (pinfunction "2_2") (pintype "passive"))
      (node (ref "R20") (pin "2") (pinfunction "2_2") (pintype "passive"))
      (node (ref "R21") (pin "2") (pinfunction "2_2") (pintype "passive"))
      (node (ref "R4") (pin "1") (pinfunction "1_1") (pintype "passive"))
      (node (ref "R5") (pin "1") (pinfunction "1_1") (pintype "passive"))
      (node (ref "R6") (pin "2") (pinfunction "2_2") (pintype "passive"))
      (node (ref "R7") (pin "2") (pinfunction "2_2") (pintype "passive"))
      (node (ref "SV1") (pin "2") (pinfunction "2_2") (pintype "passive"))
      (node (ref "SV2") (pin "10") (pinfunction "10_10") (pintype "passive"))
    )
    (net (code "62") (name "unconnected-(IC2-NC1-Pad1)") (class "Default")
      (node (ref "IC2") (pin "1") (pinfunction "NC1_1") (pintype "bidirectional"))
    )
    (net (code "63") (name "unconnected-(IC2-NC2-Pad16)") (class "Default")
      (node (ref "IC2") (pin "16") (pinfunction "NC2_16") (pintype "bidirectional"))
    )
    (net (code "64") (name "unconnected-(IC3-NC1-Pad1)") (class "Default")
      (node (ref "IC3") (pin "1") (pinfunction "NC1_1") (pintype "bidirectional"))
    )
    (net (code "65") (name "unconnected-(IC3-NC2-Pad16)") (class "Default")
      (node (ref "IC3") (pin "16") (pinfunction "NC2_16") (pintype "bidirectional"))
    )
    (net (code "66") (name "unconnected-(SV2-Pad1)") (class "Default")
      (node (ref "SV2") (pin "1") (pinfunction "1_1") (pintype "passive"))
    )
    (net (code "67") (name "unconnected-(SV2-Pad2)") (class "Default")
      (node (ref "SV2") (pin "2") (pinfunction "2_2") (pintype "passive"))
    )
    (net (code "68") (name "unconnected-(SV2-Pad3)") (class "Default")
      (node (ref "SV2") (pin "3") (pinfunction "3_3") (pintype "passive"))
    )
    (net (code "69") (name "unconnected-(SV2-Pad4)") (class "Default")
      (node (ref "SV2") (pin "4") (pinfunction "4_4") (pintype "passive"))
    )
    (net (code "70") (name "unconnected-(SV2-Pad5)") (class "Default")
      (node (ref "SV2") (pin "5") (pinfunction "5_5") (pintype "passive"))
    )
    (net (code "71") (name "unconnected-(SV2-Pad6)") (class "Default")
      (node (ref "SV2") (pin "6") (pinfunction "6_6") (pintype "passive"))
    )
  )
)
